# 09_-_CPU_-_SD_AUDIO_I2C_CAN.net
KiCad netlist of a schematic drawn in Altium Designer
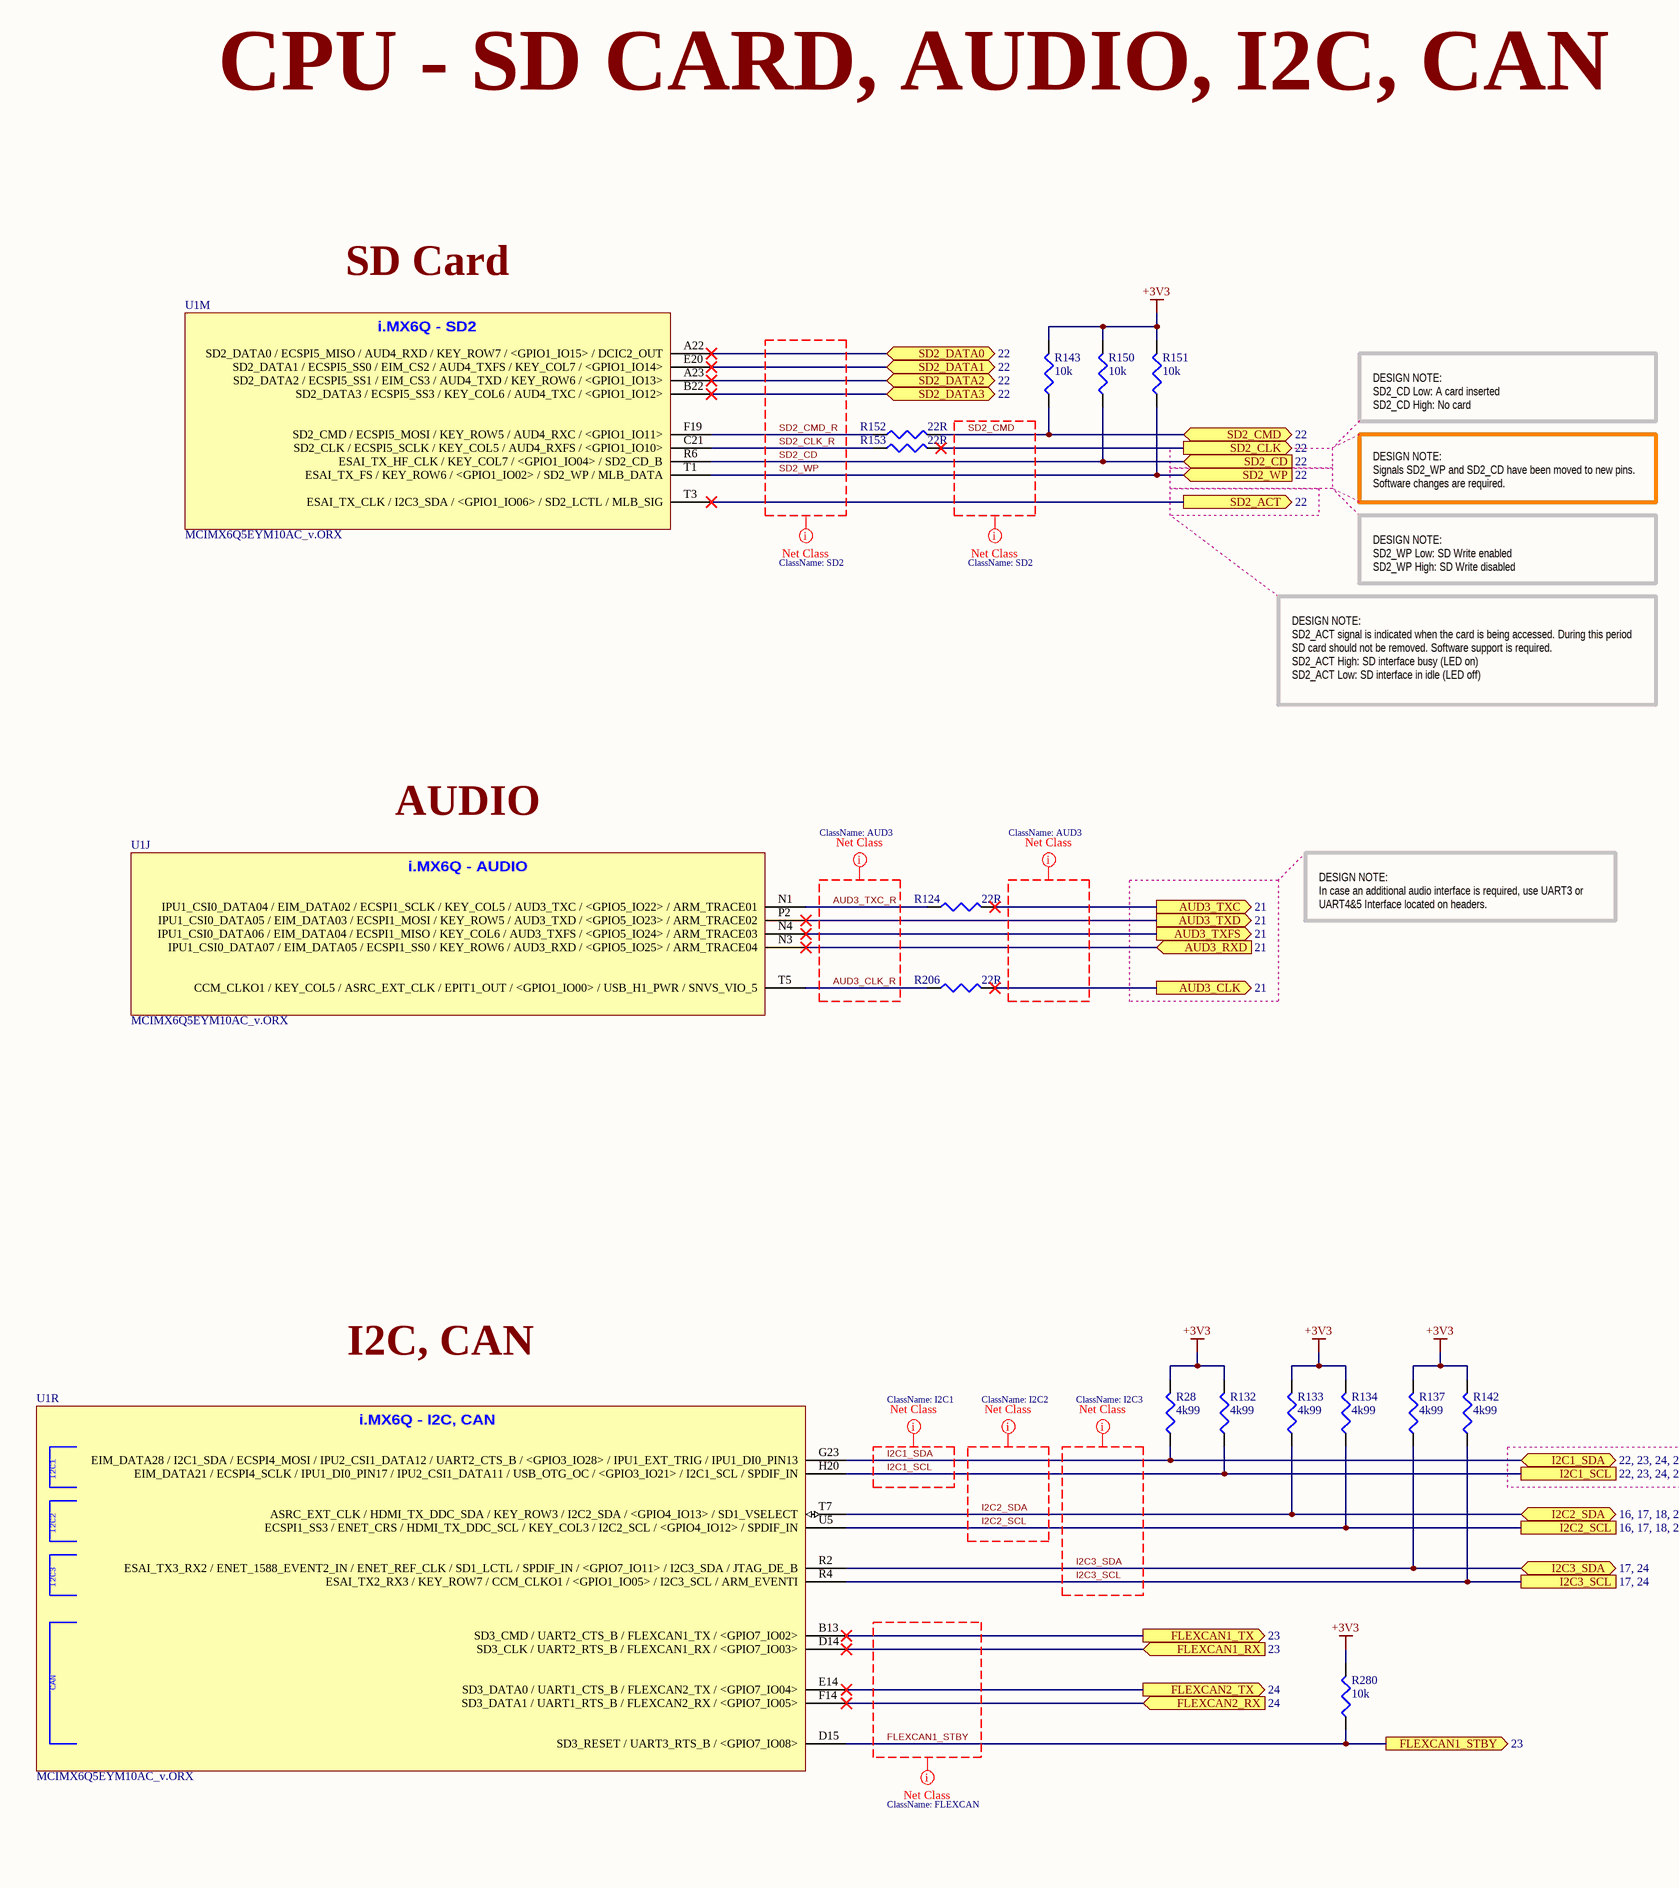
[diagram p0: [09] - CPU - SD, AUDIO, I2C, CAN.SchDoc, left]
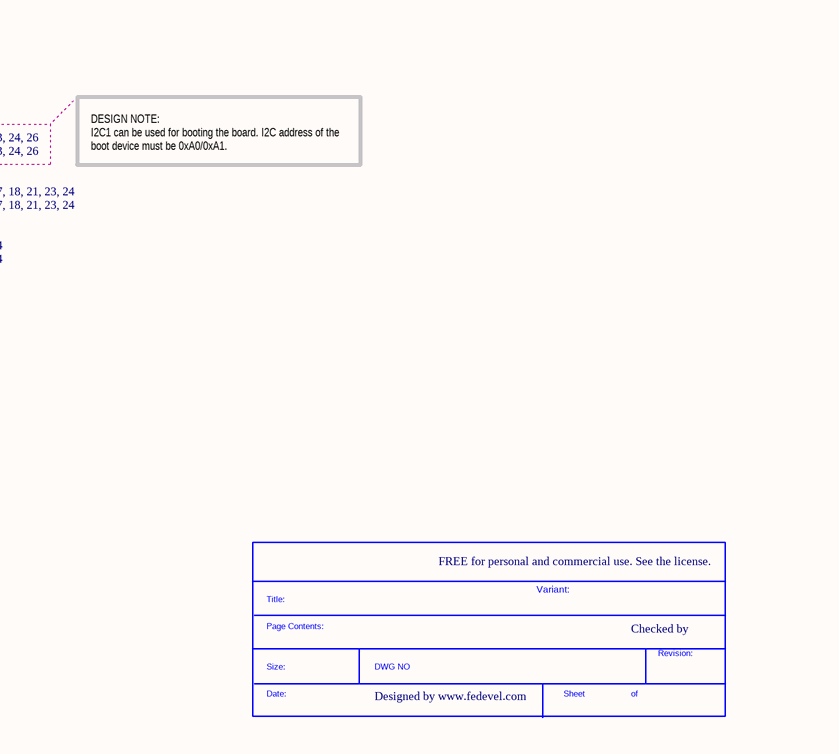
[diagram p1: [09] - CPU - SD, AUDIO, I2C, CAN.SchDoc, right]

(export (version "E")
  (design (tool "Eeschema 10.0.6"))
  (components
    (comp (ref "R28")
      (value "4k99")
      (footprint "R0402")
      (description "RES TF 4.99K OHM 1% 1/16W 0402")
      (fields
        (field (name "MANUFACTURER") "Stackpole Electronics Inc")
        (field (name "MANUFACTURER PART NUMBER") "RMCF0402FT4K99")
      )
      (libsource (lib "Integrated_Library_FEDEVEL_APR_2015") (part "RMCF0402FT4K99"))
    )
    (comp (ref "R124")
      (value "22R")
      (footprint "R0402")
      (description "RES 22.0 OHM 1/16W 1% 0402 SMD")
      (fields
        (field (name "MANUFACTURER") "Yageo")
        (field (name "MANUFACTURER PART NUMBER") "RC0402FR-0722RL")
      )
      (libsource (lib "Integrated_Library_FEDEVEL_APR_2015") (part "RC0402FR-0722RL"))
    )
    (comp (ref "R132")
      (value "4k99")
      (footprint "R0402")
      (description "RES TF 4.99K OHM 1% 1/16W 0402")
      (fields
        (field (name "MANUFACTURER") "Stackpole Electronics Inc")
        (field (name "MANUFACTURER PART NUMBER") "RMCF0402FT4K99")
      )
      (libsource (lib "Integrated_Library_FEDEVEL_APR_2015") (part "RMCF0402FT4K99"))
    )
    (comp (ref "R133")
      (value "4k99")
      (footprint "R0402")
      (description "RES TF 4.99K OHM 1% 1/16W 0402")
      (fields
        (field (name "MANUFACTURER") "Stackpole Electronics Inc")
        (field (name "MANUFACTURER PART NUMBER") "RMCF0402FT4K99")
      )
      (libsource (lib "Integrated_Library_FEDEVEL_APR_2015") (part "RMCF0402FT4K99"))
    )
    (comp (ref "R134")
      (value "4k99")
      (footprint "R0402")
      (description "RES TF 4.99K OHM 1% 1/16W 0402")
      (fields
        (field (name "MANUFACTURER") "Stackpole Electronics Inc")
        (field (name "MANUFACTURER PART NUMBER") "RMCF0402FT4K99")
      )
      (libsource (lib "Integrated_Library_FEDEVEL_APR_2015") (part "RMCF0402FT4K99"))
    )
    (comp (ref "R137")
      (value "4k99")
      (footprint "R0402")
      (description "RES TF 4.99K OHM 1% 1/16W 0402")
      (fields
        (field (name "MANUFACTURER") "Stackpole Electronics Inc")
        (field (name "MANUFACTURER PART NUMBER") "RMCF0402FT4K99")
      )
      (libsource (lib "Integrated_Library_FEDEVEL_APR_2015") (part "RMCF0402FT4K99"))
    )
    (comp (ref "R142")
      (value "4k99")
      (footprint "R0402")
      (description "RES TF 4.99K OHM 1% 1/16W 0402")
      (fields
        (field (name "MANUFACTURER") "Stackpole Electronics Inc")
        (field (name "MANUFACTURER PART NUMBER") "RMCF0402FT4K99")
      )
      (libsource (lib "Integrated_Library_FEDEVEL_APR_2015") (part "RMCF0402FT4K99"))
    )
    (comp (ref "R143")
      (value "10k")
      (footprint "R0402")
      (description "RES 10.0K OHM 1/16W 1% 0402 SMD")
      (fields
        (field (name "MANUFACTURER") "Yageo")
        (field (name "MANUFACTURER PART NUMBER") "RC0402FR-0710KL")
      )
      (libsource (lib "Integrated_Library_FEDEVEL_APR_2015") (part "RC0402FR-0710KL"))
    )
    (comp (ref "R150")
      (value "10k")
      (footprint "R0402")
      (description "RES 10.0K OHM 1/16W 1% 0402 SMD")
      (fields
        (field (name "MANUFACTURER") "Yageo")
        (field (name "MANUFACTURER PART NUMBER") "RC0402FR-0710KL")
      )
      (libsource (lib "Integrated_Library_FEDEVEL_APR_2015") (part "RC0402FR-0710KL"))
    )
    (comp (ref "R151")
      (value "10k")
      (footprint "R0402")
      (description "RES 10.0K OHM 1/16W 1% 0402 SMD")
      (fields
        (field (name "MANUFACTURER") "Yageo")
        (field (name "MANUFACTURER PART NUMBER") "RC0402FR-0710KL")
      )
      (libsource (lib "Integrated_Library_FEDEVEL_APR_2015") (part "RC0402FR-0710KL"))
    )
    (comp (ref "R152")
      (value "22R")
      (footprint "R0402")
      (description "RES 22.0 OHM 1/16W 1% 0402 SMD")
      (fields
        (field (name "MANUFACTURER") "Yageo")
        (field (name "MANUFACTURER PART NUMBER") "RC0402FR-0722RL")
      )
      (libsource (lib "Integrated_Library_FEDEVEL_APR_2015") (part "RC0402FR-0722RL"))
    )
    (comp (ref "R153")
      (value "22R")
      (footprint "R0402")
      (description "RES 22.0 OHM 1/16W 1% 0402 SMD")
      (fields
        (field (name "MANUFACTURER") "Yageo")
        (field (name "MANUFACTURER PART NUMBER") "RC0402FR-0722RL")
      )
      (libsource (lib "Integrated_Library_FEDEVEL_APR_2015") (part "RC0402FR-0722RL"))
    )
    (comp (ref "R206")
      (value "22R")
      (footprint "R0402")
      (description "RES 22.0 OHM 1/16W 1% 0402 SMD")
      (fields
        (field (name "MANUFACTURER") "Yageo")
        (field (name "MANUFACTURER PART NUMBER") "RC0402FR-0722RL")
      )
      (libsource (lib "Integrated_Library_FEDEVEL_APR_2015") (part "RC0402FR-0722RL"))
    )
    (comp (ref "R280")
      (value "10k")
      (footprint "R0402")
      (description "RES 10.0K OHM 1/16W 1% 0402 SMD")
      (fields
        (field (name "MANUFACTURER") "Yageo")
        (field (name "MANUFACTURER PART NUMBER") "RC0402FR-0710KL")
      )
      (libsource (lib "Integrated_Library_FEDEVEL_APR_2015") (part "RC0402FR-0710KL"))
    )
    (comp (ref "U1")
      (value "MCIMX6Q5EYM10AC_v.ORX")
      (footprint "PBGA624")
      (description "IC MCU 32BIT ARM QUAD 624FCBGA")
      (fields
        (field (name "MANUFACTURER") "Freescale Semiconductor")
        (field (name "MANUFACTURER PART NUMBER") "MCIMX6Q5EYM10AC")
        (field (name ".CREATOR") "MM")
        (field (name ".CHECKED PCB") "MM, checked by RF")
      )
      (libsource (lib "Integrated_Library_FEDEVEL_APR_2015") (part "MCIMX6Q5EYM10AC_v.ORX"))
    )
  )
  (nets
    (net (code "1") (name "+3V3") (class "Default")
      (node (ref "R132") (pin "2") (pinfunction "2_2") (pintype "passive"))
      (node (ref "R133") (pin "2") (pinfunction "2_2") (pintype "passive"))
      (node (ref "R134") (pin "2") (pinfunction "2_2") (pintype "passive"))
      (node (ref "R137") (pin "2") (pinfunction "2_2") (pintype "passive"))
      (node (ref "R142") (pin "2") (pinfunction "2_2") (pintype "passive"))
      (node (ref "R143") (pin "2") (pinfunction "2_2") (pintype "passive"))
      (node (ref "R150") (pin "2") (pinfunction "2_2") (pintype "passive"))
      (node (ref "R151") (pin "2") (pinfunction "2_2") (pintype "passive"))
      (node (ref "R28") (pin "2") (pinfunction "2_2") (pintype "passive"))
      (node (ref "R280") (pin "2") (pinfunction "2_2") (pintype "passive"))
    )
    (net (code "2") (name "/AUD3_CLK") (class "Default")
      (node (ref "R206") (pin "2") (pinfunction "2_2") (pintype "passive+no_connect"))
    )
    (net (code "3") (name "/AUD3_CLK_R") (class "Default")
      (node (ref "R206") (pin "1") (pinfunction "1_1") (pintype "passive"))
      (node (ref "U1") (pin "T5") (pinfunction "CCM_CLKO1_/_KEY_COL5_/_ASRC_EXT_CLK_/_EPIT1_OUT_/_<GPIO1_IO00>_/_USB_H1_PWR_/_SNVS_VIO_5_T5") (pintype "passive"))
    )
    (net (code "4") (name "/AUD3_RXD") (class "Default")
      (node (ref "U1") (pin "N3") (pinfunction "IPU1_CSI0_DATA07_/_EIM_DATA05_/_ECSPI1_SS0_/_KEY_ROW6_/_AUD3_RXD_/_<GPIO5_IO25>_/_ARM_TRACE04_N3") (pintype "passive+no_connect"))
    )
    (net (code "5") (name "/AUD3_TXC") (class "Default")
      (node (ref "R124") (pin "2") (pinfunction "2_2") (pintype "passive+no_connect"))
    )
    (net (code "6") (name "/AUD3_TXC_R") (class "Default")
      (node (ref "R124") (pin "1") (pinfunction "1_1") (pintype "passive"))
      (node (ref "U1") (pin "N1") (pinfunction "IPU1_CSI0_DATA04_/_EIM_DATA02_/_ECSPI1_SCLK_/_KEY_COL5_/_AUD3_TXC_/_<GPIO5_IO22>_/_ARM_TRACE01_N1") (pintype "passive"))
    )
    (net (code "7") (name "/AUD3_TXD") (class "Default")
      (node (ref "U1") (pin "P2") (pinfunction "IPU1_CSI0_DATA05_/_EIM_DATA03_/_ECSPI1_MOSI_/_KEY_ROW5_/_AUD3_TXD_/_<GPIO5_IO23>_/_ARM_TRACE02_P2") (pintype "passive+no_connect"))
    )
    (net (code "8") (name "/AUD3_TXFS") (class "Default")
      (node (ref "U1") (pin "N4") (pinfunction "IPU1_CSI0_DATA06_/_EIM_DATA04_/_ECSPI1_MISO_/_KEY_COL6_/_AUD3_TXFS_/_<GPIO5_IO24>_/_ARM_TRACE03_N4") (pintype "passive+no_connect"))
    )
    (net (code "9") (name "/FLEXCAN1_RX") (class "Default")
      (node (ref "U1") (pin "D14") (pinfunction "SD3_CLK_/_UART2_RTS_B_/_FLEXCAN1_RX_/_<GPIO7_IO03>_D14") (pintype "passive+no_connect"))
    )
    (net (code "10") (name "/FLEXCAN1_STBY") (class "Default")
      (node (ref "R280") (pin "1") (pinfunction "1_1") (pintype "passive"))
      (node (ref "U1") (pin "D15") (pinfunction "SD3_RESET_/_UART3_RTS_B_/_<GPIO7_IO08>_D15") (pintype "passive"))
    )
    (net (code "11") (name "/FLEXCAN1_TX") (class "Default")
      (node (ref "U1") (pin "B13") (pinfunction "SD3_CMD_/_UART2_CTS_B_/_FLEXCAN1_TX_/_<GPIO7_IO02>_B13") (pintype "passive+no_connect"))
    )
    (net (code "12") (name "/FLEXCAN2_RX") (class "Default")
      (node (ref "U1") (pin "F14") (pinfunction "SD3_DATA1_/_UART1_RTS_B_/_FLEXCAN2_RX_/_<GPIO7_IO05>_F14") (pintype "passive+no_connect"))
    )
    (net (code "13") (name "/FLEXCAN2_TX") (class "Default")
      (node (ref "U1") (pin "E14") (pinfunction "SD3_DATA0_/_UART1_CTS_B_/_FLEXCAN2_TX_/_<GPIO7_IO04>_E14") (pintype "passive+no_connect"))
    )
    (net (code "14") (name "/I2C1_SCL") (class "Default")
      (node (ref "R132") (pin "1") (pinfunction "1_1") (pintype "passive"))
      (node (ref "U1") (pin "H20") (pinfunction "EIM_DATA21_/_ECSPI4_SCLK_/_IPU1_DI0_PIN17_/_IPU2_CSI1_DATA11_/_USB_OTG_OC_/_<GPIO3_IO21>_/_I2C1_SCL_/_SPDIF_IN_H20") (pintype "passive"))
    )
    (net (code "15") (name "/I2C1_SDA") (class "Default")
      (node (ref "R28") (pin "1") (pinfunction "1_1") (pintype "passive"))
      (node (ref "U1") (pin "G23") (pinfunction "EIM_DATA28_/_I2C1_SDA_/_ECSPI4_MOSI_/_IPU2_CSI1_DATA12_/_UART2_CTS_B_/_<GPIO3_IO28>_/_IPU1_EXT_TRIG_/_IPU1_DI0_PIN13_G23") (pintype "passive"))
    )
    (net (code "16") (name "/I2C2_SCL") (class "Default")
      (node (ref "R134") (pin "1") (pinfunction "1_1") (pintype "passive"))
      (node (ref "U1") (pin "U5") (pinfunction "ECSPI1_SS3_/_ENET_CRS_/_HDMI_TX_DDC_SCL_/_KEY_COL3_/_I2C2_SCL_/_<GPIO4_IO12>_/_SPDIF_IN_U5") (pintype "passive"))
    )
    (net (code "17") (name "/I2C2_SDA") (class "Default")
      (node (ref "R133") (pin "1") (pinfunction "1_1") (pintype "passive"))
      (node (ref "U1") (pin "T7") (pinfunction "ASRC_EXT_CLK_/_HDMI_TX_DDC_SDA_/_KEY_ROW3_/_I2C2_SDA_/_<GPIO4_IO13>_/_SD1_VSELECT_T7") (pintype "bidirectional"))
    )
    (net (code "18") (name "/I2C3_SCL") (class "Default")
      (node (ref "R142") (pin "1") (pinfunction "1_1") (pintype "passive"))
      (node (ref "U1") (pin "R4") (pinfunction "ESAI_TX2_RX3_/_KEY_ROW7_/_CCM_CLKO1_/_<GPIO1_IO05>_/_I2C3_SCL_/_ARM_EVENTI_R4") (pintype "passive"))
    )
    (net (code "19") (name "/I2C3_SDA") (class "Default")
      (node (ref "R137") (pin "1") (pinfunction "1_1") (pintype "passive"))
      (node (ref "U1") (pin "R2") (pinfunction "ESAI_TX3_RX2_/_ENET_1588_EVENT2_IN_/_ENET_REF_CLK_/_SD1_LCTL_/_SPDIF_IN_/_<GPIO7_IO11>_/_I2C3_SDA_/_JTAG_DE_B_R2") (pintype "passive"))
    )
    (net (code "20") (name "/SD2_ACT") (class "Default")
      (node (ref "U1") (pin "T3") (pinfunction "ESAI_TX_CLK_/_I2C3_SDA_/_<GPIO1_IO06>_/_SD2_LCTL_/_MLB_SIG_T3") (pintype "passive+no_connect"))
    )
    (net (code "21") (name "/SD2_CD") (class "Default")
      (node (ref "R150") (pin "1") (pinfunction "1_1") (pintype "passive"))
      (node (ref "U1") (pin "R6") (pinfunction "ESAI_TX_HF_CLK_/_KEY_COL7_/_<GPIO1_IO04>_/_SD2_CD_B_R6") (pintype "passive"))
    )
    (net (code "22") (name "/SD2_CLK") (class "Default")
      (node (ref "R153") (pin "2") (pinfunction "2_2") (pintype "passive+no_connect"))
    )
    (net (code "23") (name "/SD2_CLK_R") (class "Default")
      (node (ref "R153") (pin "1") (pinfunction "1_1") (pintype "passive"))
      (node (ref "U1") (pin "C21") (pinfunction "SD2_CLK_/_ECSPI5_SCLK_/_KEY_COL5_/_AUD4_RXFS_/_<GPIO1_IO10>_C21") (pintype "passive"))
    )
    (net (code "24") (name "/SD2_CMD") (class "Default")
      (node (ref "R143") (pin "1") (pinfunction "1_1") (pintype "passive"))
      (node (ref "R152") (pin "2") (pinfunction "2_2") (pintype "passive"))
    )
    (net (code "25") (name "/SD2_CMD_R") (class "Default")
      (node (ref "R152") (pin "1") (pinfunction "1_1") (pintype "passive"))
      (node (ref "U1") (pin "F19") (pinfunction "SD2_CMD_/_ECSPI5_MOSI_/_KEY_ROW5_/_AUD4_RXC_/_<GPIO1_IO11>_F19") (pintype "passive"))
    )
    (net (code "26") (name "/SD2_DATA0") (class "Default")
      (node (ref "U1") (pin "A22") (pinfunction "SD2_DATA0_/_ECSPI5_MISO_/_AUD4_RXD_/_KEY_ROW7_/_<GPIO1_IO15>_/_DCIC2_OUT_A22") (pintype "passive+no_connect"))
    )
    (net (code "27") (name "/SD2_DATA1") (class "Default")
      (node (ref "U1") (pin "E20") (pinfunction "SD2_DATA1_/_ECSPI5_SS0_/_EIM_CS2_/_AUD4_TXFS_/_KEY_COL7_/_<GPIO1_IO14>_E20") (pintype "passive+no_connect"))
    )
    (net (code "28") (name "/SD2_DATA2") (class "Default")
      (node (ref "U1") (pin "A23") (pinfunction "SD2_DATA2_/_ECSPI5_SS1_/_EIM_CS3_/_AUD4_TXD_/_KEY_ROW6_/_<GPIO1_IO13>_A23") (pintype "passive+no_connect"))
    )
    (net (code "29") (name "/SD2_DATA3") (class "Default")
      (node (ref "U1") (pin "B22") (pinfunction "SD2_DATA3_/_ECSPI5_SS3_/_KEY_COL6_/_AUD4_TXC_/_<GPIO1_IO12>_B22") (pintype "passive+no_connect"))
    )
    (net (code "30") (name "/SD2_WP") (class "Default")
      (node (ref "R151") (pin "1") (pinfunction "1_1") (pintype "passive"))
      (node (ref "U1") (pin "T1") (pinfunction "ESAI_TX_FS_/_KEY_ROW6_/_<GPIO1_IO02>_/_SD2_WP_/_MLB_DATA_T1") (pintype "passive"))
    )
  )
)
